# 549-jmaccarl.net
KiCad netlist of a schematic drawn in EAGLE
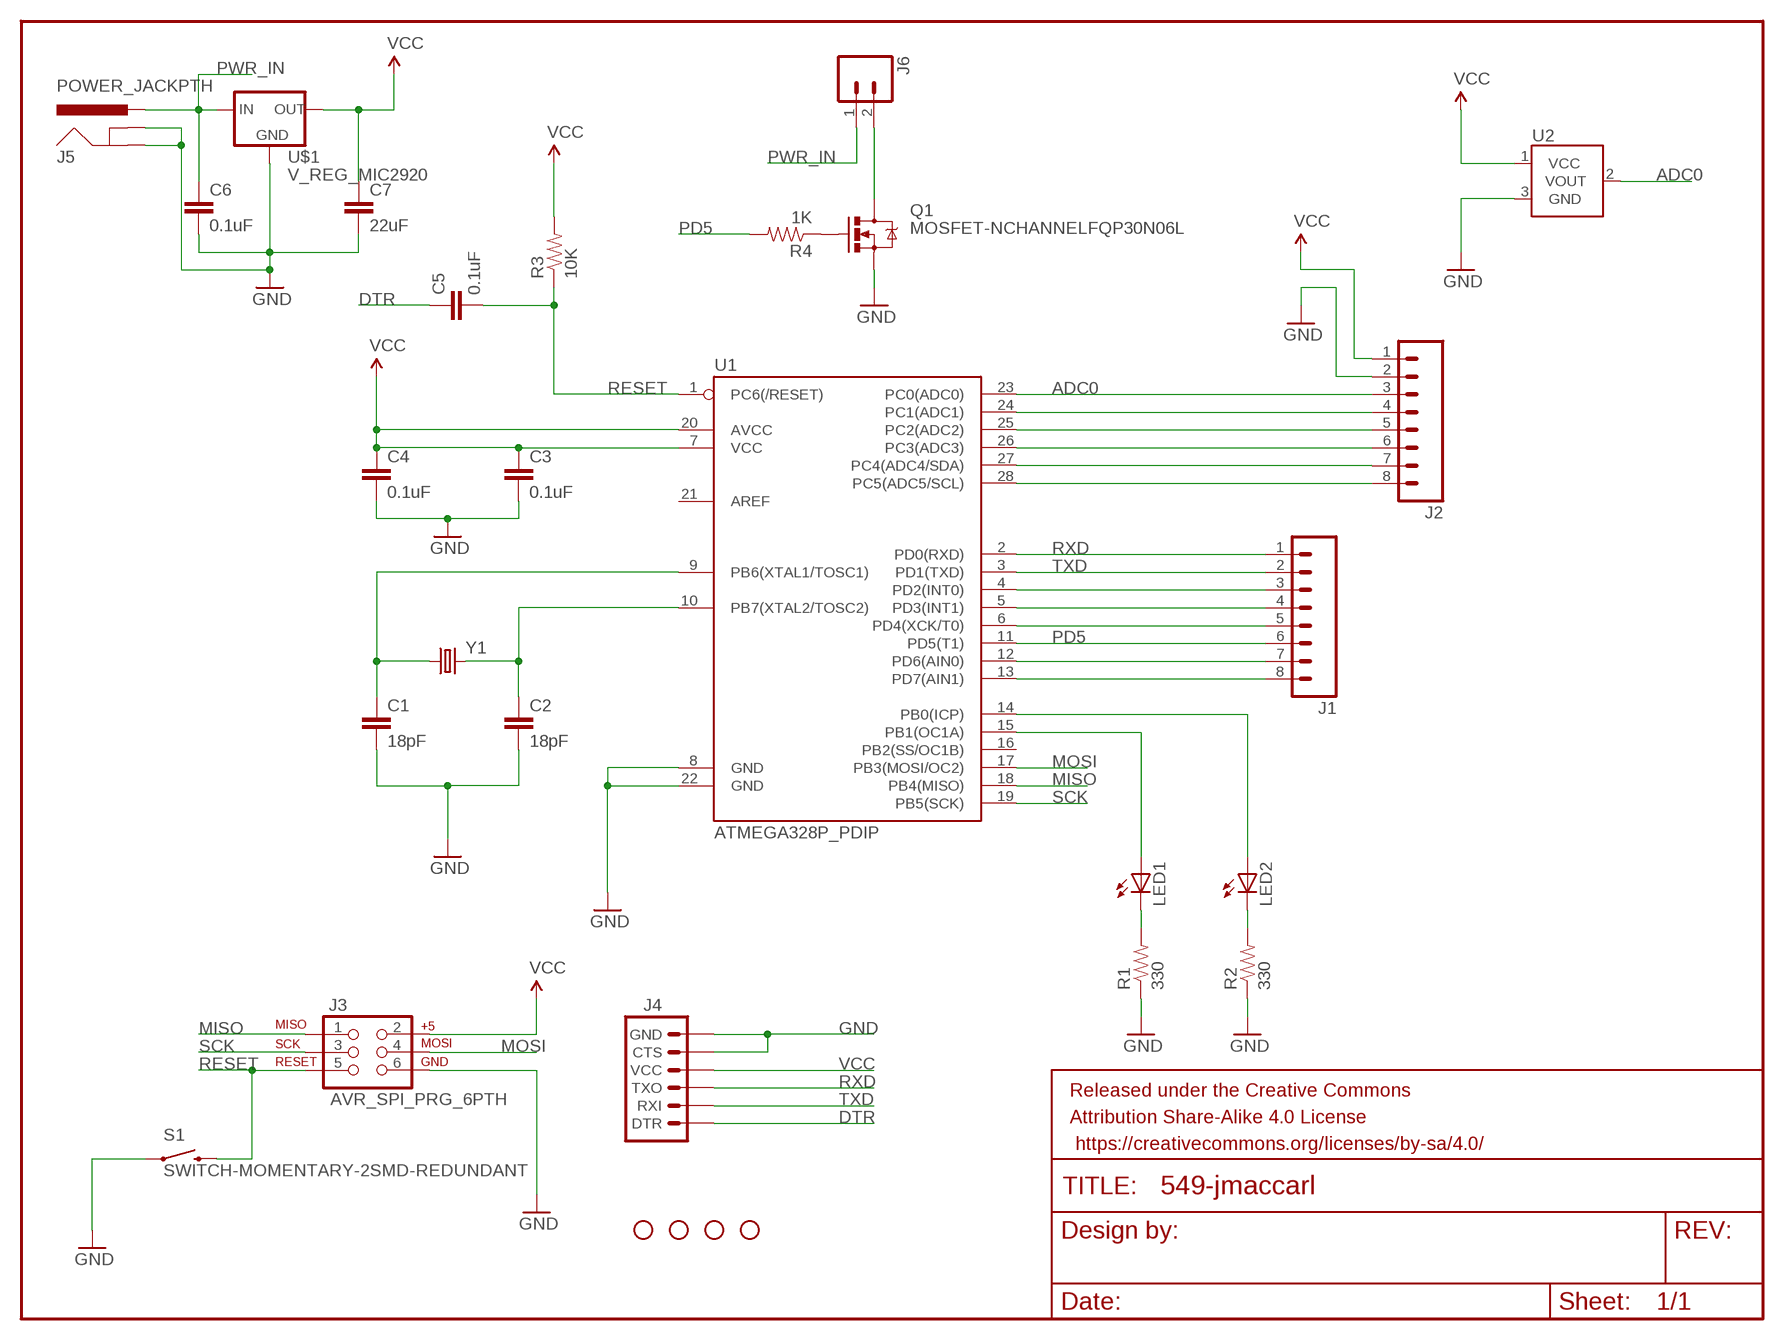
[diagram p0: schematic, sheet 1]

(export (version "E")
  (design (tool "Eeschema 10.0.6"))
  (components
    (comp (ref "C1")
      (value "18pF")
      (footprint "eagle-import:1206")
      (libsource (lib "eagle-import") (part "CAP1206"))
    )
    (comp (ref "C2")
      (value "18pF")
      (footprint "eagle-import:1206")
      (libsource (lib "eagle-import") (part "CAP1206"))
    )
    (comp (ref "C3")
      (value "0.1uF")
      (footprint "eagle-import:1206")
      (libsource (lib "eagle-import") (part "CAP1206"))
    )
    (comp (ref "C4")
      (value "0.1uF")
      (footprint "eagle-import:1206")
      (libsource (lib "eagle-import") (part "CAP1206"))
    )
    (comp (ref "C5")
      (value "0.1uF")
      (footprint "eagle-import:1206")
      (libsource (lib "eagle-import") (part "CAP1206"))
    )
    (comp (ref "C6")
      (value "0.1uF")
      (footprint "eagle-import:1206")
      (libsource (lib "eagle-import") (part "CAP1206"))
    )
    (comp (ref "C7")
      (value "22uF")
      (footprint "eagle-import:1206")
      (libsource (lib "eagle-import") (part "CAP1206"))
    )
    (comp (ref "FRAME1")
      (value "FRAME-LETTER")
      (footprint "eagle-import:CREATIVE_COMMONS")
      (libsource (lib "eagle-import") (part "FRAME-LETTER"))
    )
    (comp (ref "H1")
      (value "STAND-OFF")
      (footprint "eagle-import:STAND-OFF")
      (libsource (lib "eagle-import") (part "STAND-OFF"))
    )
    (comp (ref "H2")
      (value "STAND-OFF")
      (footprint "eagle-import:STAND-OFF")
      (libsource (lib "eagle-import") (part "STAND-OFF"))
    )
    (comp (ref "H3")
      (value "STAND-OFF")
      (footprint "eagle-import:STAND-OFF")
      (libsource (lib "eagle-import") (part "STAND-OFF"))
    )
    (comp (ref "H4")
      (value "STAND-OFF")
      (footprint "eagle-import:STAND-OFF")
      (libsource (lib "eagle-import") (part "STAND-OFF"))
    )
    (comp (ref "J1")
      (value "M08LOCK")
      (footprint "eagle-import:1X08_LOCK")
      (libsource (lib "eagle-import") (part "M08LOCK"))
    )
    (comp (ref "J2")
      (value "M08LOCK")
      (footprint "eagle-import:1X08_LOCK")
      (libsource (lib "eagle-import") (part "M08LOCK"))
    )
    (comp (ref "J3")
      (value "AVR_SPI_PRG_6PTH")
      (footprint "eagle-import:2X3")
      (libsource (lib "eagle-import") (part "AVR_SPI_PRG_6PTH"))
    )
    (comp (ref "J4")
      (value "ARDUINO_SERIAL_PROGRAMPTH")
      (footprint "eagle-import:1X06")
      (libsource (lib "eagle-import") (part "ARDUINO_SERIAL_PROGRAMPTH"))
    )
    (comp (ref "J5")
      (value "POWER_JACKPTH")
      (footprint "eagle-import:POWER_JACK_PTH")
      (libsource (lib "eagle-import") (part "POWER_JACKPTH"))
    )
    (comp (ref "J6")
      (value "M025MM")
      (footprint "eagle-import:SCREWTERMINAL-5MM-2")
      (libsource (lib "eagle-import") (part "M025MM"))
    )
    (comp (ref "LED1")
      (value "LED1206")
      (footprint "eagle-import:LED-1206")
      (libsource (lib "eagle-import") (part "LED1206"))
    )
    (comp (ref "LED2")
      (value "LED1206")
      (footprint "eagle-import:LED-1206")
      (libsource (lib "eagle-import") (part "LED1206"))
    )
    (comp (ref "Q1")
      (value "MOSFET-NCHANNELFQP30N06L")
      (footprint "eagle-import:TO220V")
      (libsource (lib "eagle-import") (part "MOSFET-NCHANNELFQP30N06L"))
    )
    (comp (ref "R1")
      (value "330")
      (footprint "eagle-import:1206")
      (libsource (lib "eagle-import") (part "RESISTOR1206"))
    )
    (comp (ref "R2")
      (value "330")
      (footprint "eagle-import:1206")
      (libsource (lib "eagle-import") (part "RESISTOR1206"))
    )
    (comp (ref "R3")
      (value "10K")
      (footprint "eagle-import:1206")
      (libsource (lib "eagle-import") (part "RESISTOR1206"))
    )
    (comp (ref "R4")
      (value "1K")
      (footprint "eagle-import:1206")
      (libsource (lib "eagle-import") (part "RESISTOR1206"))
    )
    (comp (ref "S1")
      (value "SWITCH-MOMENTARY-2SMD-REDUNDANT")
      (footprint "eagle-import:TACTILE-SWITCH-SMD")
      (libsource (lib "eagle-import") (part "SWITCH-MOMENTARY-2SMD-REDUNDANT"))
    )
    (comp (ref "U$1")
      (value "V_REG_MIC2920")
      (footprint "eagle-import:SOT223")
      (libsource (lib "eagle-import") (part "V_REG_MIC2920"))
    )
    (comp (ref "U1")
      (value "ATMEGA328P_PDIP")
      (footprint "eagle-import:DIL28-3")
      (libsource (lib "eagle-import") (part "ATMEGA328P_PDIP"))
    )
    (comp (ref "U2")
      (value "TMP36GT9")
      (footprint "eagle-import:TO-92")
      (libsource (lib "eagle-import") (part "TMP36GT9"))
    )
    (comp (ref "Y1")
      (value "CRYSTALTXC-7A")
      (footprint "eagle-import:CRYSTAL-TXC-7A")
      (libsource (lib "eagle-import") (part "CRYSTALTXC-7A"))
    )
  )
  (nets
    (net (code "1") (name "/ADC0") (class "Default")
      (node (ref "J2") (pin "3") (pinfunction "3_3") (pintype "passive"))
      (node (ref "U1") (pin "23") (pinfunction "PC0(ADC0)_23") (pintype "bidirectional"))
      (node (ref "U2") (pin "2") (pinfunction "VOUT_2") (pintype "bidirectional"))
    )
    (net (code "2") (name "/DTR") (class "Default")
      (node (ref "C5") (pin "1") (pinfunction "1_1") (pintype "passive"))
      (node (ref "J4") (pin "1") (pinfunction "DTR_1") (pintype "passive"))
    )
    (net (code "3") (name "/MISO") (class "Default")
      (node (ref "J3") (pin "1") (pinfunction "1_1") (pintype "passive"))
      (node (ref "U1") (pin "18") (pinfunction "PB4(MISO)_18") (pintype "bidirectional"))
    )
    (net (code "4") (name "/MOSI") (class "Default")
      (node (ref "J3") (pin "4") (pinfunction "4_4") (pintype "passive"))
      (node (ref "U1") (pin "17") (pinfunction "PB3(MOSI/OC2)_17") (pintype "bidirectional"))
    )
    (net (code "5") (name "/PD5") (class "Default")
      (node (ref "J1") (pin "6") (pinfunction "6_6") (pintype "passive"))
      (node (ref "R4") (pin "2") (pinfunction "2_2") (pintype "passive"))
      (node (ref "U1") (pin "11") (pinfunction "PD5(T1)_11") (pintype "bidirectional"))
    )
    (net (code "6") (name "/PWR_IN") (class "Default")
      (node (ref "C6") (pin "1") (pinfunction "1_1") (pintype "passive"))
      (node (ref "J5") (pin "PWR") (pinfunction "PWR_PWR") (pintype "bidirectional"))
      (node (ref "J6") (pin "1") (pinfunction "1_1") (pintype "passive"))
      (node (ref "U$1") (pin "1") (pinfunction "IN_1") (pintype "input"))
    )
    (net (code "7") (name "/RESET") (class "Default")
      (node (ref "C5") (pin "2") (pinfunction "2_2") (pintype "passive"))
      (node (ref "J3") (pin "5") (pinfunction "5_5") (pintype "passive"))
      (node (ref "R3") (pin "1") (pinfunction "1_1") (pintype "passive"))
      (node (ref "S1") (pin "3") (pinfunction "2_3") (pintype "passive"))
      (node (ref "S1") (pin "4") (pinfunction "2_4") (pintype "passive"))
      (node (ref "U1") (pin "1") (pinfunction "PC6(/RESET)_1") (pintype "bidirectional"))
    )
    (net (code "8") (name "/RXD") (class "Default")
      (node (ref "J1") (pin "1") (pinfunction "1_1") (pintype "passive"))
      (node (ref "J4") (pin "3") (pinfunction "TXO_3") (pintype "passive"))
      (node (ref "U1") (pin "2") (pinfunction "PD0(RXD)_2") (pintype "bidirectional"))
    )
    (net (code "9") (name "/SCK") (class "Default")
      (node (ref "J3") (pin "3") (pinfunction "3_3") (pintype "passive"))
      (node (ref "U1") (pin "19") (pinfunction "PB5(SCK)_19") (pintype "bidirectional"))
    )
    (net (code "10") (name "/TXD") (class "Default")
      (node (ref "J1") (pin "2") (pinfunction "2_2") (pintype "passive"))
      (node (ref "J4") (pin "2") (pinfunction "RXI_2") (pintype "passive"))
      (node (ref "U1") (pin "3") (pinfunction "PD1(TXD)_3") (pintype "bidirectional"))
    )
    (net (code "11") (name "GND") (class "Default")
      (node (ref "C1") (pin "2") (pinfunction "2_2") (pintype "passive"))
      (node (ref "C2") (pin "2") (pinfunction "2_2") (pintype "passive"))
      (node (ref "C3") (pin "2") (pinfunction "2_2") (pintype "passive"))
      (node (ref "C4") (pin "2") (pinfunction "2_2") (pintype "passive"))
      (node (ref "C6") (pin "2") (pinfunction "2_2") (pintype "passive"))
      (node (ref "C7") (pin "2") (pinfunction "2_2") (pintype "passive"))
      (node (ref "J2") (pin "2") (pinfunction "2_2") (pintype "passive"))
      (node (ref "J3") (pin "6") (pinfunction "6_6") (pintype "passive"))
      (node (ref "J4") (pin "5") (pinfunction "CTS_5") (pintype "passive"))
      (node (ref "J4") (pin "6") (pinfunction "GND_6") (pintype "passive"))
      (node (ref "J5") (pin "GND") (pinfunction "GND_GND") (pintype "bidirectional"))
      (node (ref "J5") (pin "GNDBREAK") (pinfunction "GNDBREAK_GNDBREAK") (pintype "bidirectional"))
      (node (ref "Q1") (pin "3") (pinfunction "S_3") (pintype "passive"))
      (node (ref "R1") (pin "1") (pinfunction "1_1") (pintype "passive"))
      (node (ref "R2") (pin "1") (pinfunction "1_1") (pintype "passive"))
      (node (ref "S1") (pin "1") (pinfunction "1_1") (pintype "passive"))
      (node (ref "S1") (pin "2") (pinfunction "1_2") (pintype "passive"))
      (node (ref "U$1") (pin "2") (pinfunction "GND_2") (pintype "input"))
      (node (ref "U1") (pin "22") (pinfunction "GND_22") (pintype "bidirectional"))
      (node (ref "U1") (pin "8") (pinfunction "GND_8") (pintype "bidirectional"))
      (node (ref "U2") (pin "3") (pinfunction "GND_3") (pintype "bidirectional"))
    )
    (net (code "12") (name "Net-(LED1-PadC)") (class "Default")
      (node (ref "LED1") (pin "C") (pinfunction "C_C") (pintype "passive"))
      (node (ref "R1") (pin "2") (pinfunction "2_2") (pintype "passive"))
    )
    (net (code "13") (name "Net-(LED2-PadC)") (class "Default")
      (node (ref "LED2") (pin "C") (pinfunction "C_C") (pintype "passive"))
      (node (ref "R2") (pin "2") (pinfunction "2_2") (pintype "passive"))
    )
    (net (code "14") (name "Net-(Q1-D)") (class "Default")
      (node (ref "J6") (pin "2") (pinfunction "2_2") (pintype "passive"))
      (node (ref "Q1") (pin "2") (pinfunction "D_2") (pintype "passive"))
    )
    (net (code "15") (name "Net-(Q1-G)") (class "Default")
      (node (ref "Q1") (pin "1") (pinfunction "G_1") (pintype "passive"))
      (node (ref "R4") (pin "1") (pinfunction "1_1") (pintype "passive"))
    )
    (net (code "16") (name "Net-(U1-PB0(ICP))") (class "Default")
      (node (ref "LED2") (pin "A") (pinfunction "A_A") (pintype "passive"))
      (node (ref "U1") (pin "14") (pinfunction "PB0(ICP)_14") (pintype "bidirectional"))
    )
    (net (code "17") (name "Net-(U1-PB1(OC1A))") (class "Default")
      (node (ref "LED1") (pin "A") (pinfunction "A_A") (pintype "passive"))
      (node (ref "U1") (pin "15") (pinfunction "PB1(OC1A)_15") (pintype "bidirectional"))
    )
    (net (code "18") (name "Net-(U1-PB6(XTAL1{slash}TOSC1))") (class "Default")
      (node (ref "C1") (pin "1") (pinfunction "1_1") (pintype "passive"))
      (node (ref "U1") (pin "9") (pinfunction "PB6(XTAL1/TOSC1)_9") (pintype "bidirectional"))
      (node (ref "Y1") (pin "P$1") (pinfunction "1_P$1") (pintype "passive"))
    )
    (net (code "19") (name "Net-(U1-PB7(XTAL2{slash}TOSC2))") (class "Default")
      (node (ref "C2") (pin "1") (pinfunction "1_1") (pintype "passive"))
      (node (ref "U1") (pin "10") (pinfunction "PB7(XTAL2/TOSC2)_10") (pintype "bidirectional"))
      (node (ref "Y1") (pin "P$2") (pinfunction "2_P$2") (pintype "passive"))
    )
    (net (code "20") (name "Net-(U1-PC1(ADC1))") (class "Default")
      (node (ref "J2") (pin "4") (pinfunction "4_4") (pintype "passive"))
      (node (ref "U1") (pin "24") (pinfunction "PC1(ADC1)_24") (pintype "bidirectional"))
    )
    (net (code "21") (name "Net-(U1-PC2(ADC2))") (class "Default")
      (node (ref "J2") (pin "5") (pinfunction "5_5") (pintype "passive"))
      (node (ref "U1") (pin "25") (pinfunction "PC2(ADC2)_25") (pintype "bidirectional"))
    )
    (net (code "22") (name "Net-(U1-PC3(ADC3))") (class "Default")
      (node (ref "J2") (pin "6") (pinfunction "6_6") (pintype "passive"))
      (node (ref "U1") (pin "26") (pinfunction "PC3(ADC3)_26") (pintype "bidirectional"))
    )
    (net (code "23") (name "Net-(U1-PC4(ADC4{slash}SDA))") (class "Default")
      (node (ref "J2") (pin "7") (pinfunction "7_7") (pintype "passive"))
      (node (ref "U1") (pin "27") (pinfunction "PC4(ADC4/SDA)_27") (pintype "bidirectional"))
    )
    (net (code "24") (name "Net-(U1-PC5(ADC5{slash}SCL))") (class "Default")
      (node (ref "J2") (pin "8") (pinfunction "8_8") (pintype "passive"))
      (node (ref "U1") (pin "28") (pinfunction "PC5(ADC5/SCL)_28") (pintype "bidirectional"))
    )
    (net (code "25") (name "Net-(U1-PD2(INT0))") (class "Default")
      (node (ref "J1") (pin "3") (pinfunction "3_3") (pintype "passive"))
      (node (ref "U1") (pin "4") (pinfunction "PD2(INT0)_4") (pintype "bidirectional"))
    )
    (net (code "26") (name "Net-(U1-PD3(INT1))") (class "Default")
      (node (ref "J1") (pin "4") (pinfunction "4_4") (pintype "passive"))
      (node (ref "U1") (pin "5") (pinfunction "PD3(INT1)_5") (pintype "bidirectional"))
    )
    (net (code "27") (name "Net-(U1-PD4(XCK{slash}T0))") (class "Default")
      (node (ref "J1") (pin "5") (pinfunction "5_5") (pintype "passive"))
      (node (ref "U1") (pin "6") (pinfunction "PD4(XCK/T0)_6") (pintype "bidirectional"))
    )
    (net (code "28") (name "Net-(U1-PD6(AIN0))") (class "Default")
      (node (ref "J1") (pin "7") (pinfunction "7_7") (pintype "passive"))
      (node (ref "U1") (pin "12") (pinfunction "PD6(AIN0)_12") (pintype "bidirectional"))
    )
    (net (code "29") (name "Net-(U1-PD7(AIN1))") (class "Default")
      (node (ref "J1") (pin "8") (pinfunction "8_8") (pintype "passive"))
      (node (ref "U1") (pin "13") (pinfunction "PD7(AIN1)_13") (pintype "bidirectional"))
    )
    (net (code "30") (name "VCC") (class "Default")
      (node (ref "C3") (pin "1") (pinfunction "1_1") (pintype "passive"))
      (node (ref "C4") (pin "1") (pinfunction "1_1") (pintype "passive"))
      (node (ref "C7") (pin "1") (pinfunction "1_1") (pintype "passive"))
      (node (ref "J2") (pin "1") (pinfunction "1_1") (pintype "passive"))
      (node (ref "J3") (pin "2") (pinfunction "2_2") (pintype "passive"))
      (node (ref "J4") (pin "4") (pinfunction "VCC_4") (pintype "passive"))
      (node (ref "R3") (pin "2") (pinfunction "2_2") (pintype "passive"))
      (node (ref "U$1") (pin "3") (pinfunction "OUT_3") (pintype "passive"))
      (node (ref "U1") (pin "20") (pinfunction "AVCC_20") (pintype "bidirectional"))
      (node (ref "U1") (pin "7") (pinfunction "VCC_7") (pintype "bidirectional"))
      (node (ref "U2") (pin "1") (pinfunction "VCC_1") (pintype "bidirectional"))
    )
    (net (code "31") (name "unconnected-(U1-AREF-Pad21)") (class "Default")
      (node (ref "U1") (pin "21") (pinfunction "AREF_21") (pintype "bidirectional"))
    )
    (net (code "32") (name "unconnected-(U1-PB2(SS{slash}OC1B)-Pad16)") (class "Default")
      (node (ref "U1") (pin "16") (pinfunction "PB2(SS/OC1B)_16") (pintype "bidirectional"))
    )
  )
)
